# SCH_-_Power_Connector.net
KiCad netlist of a schematic drawn in Altium Designer
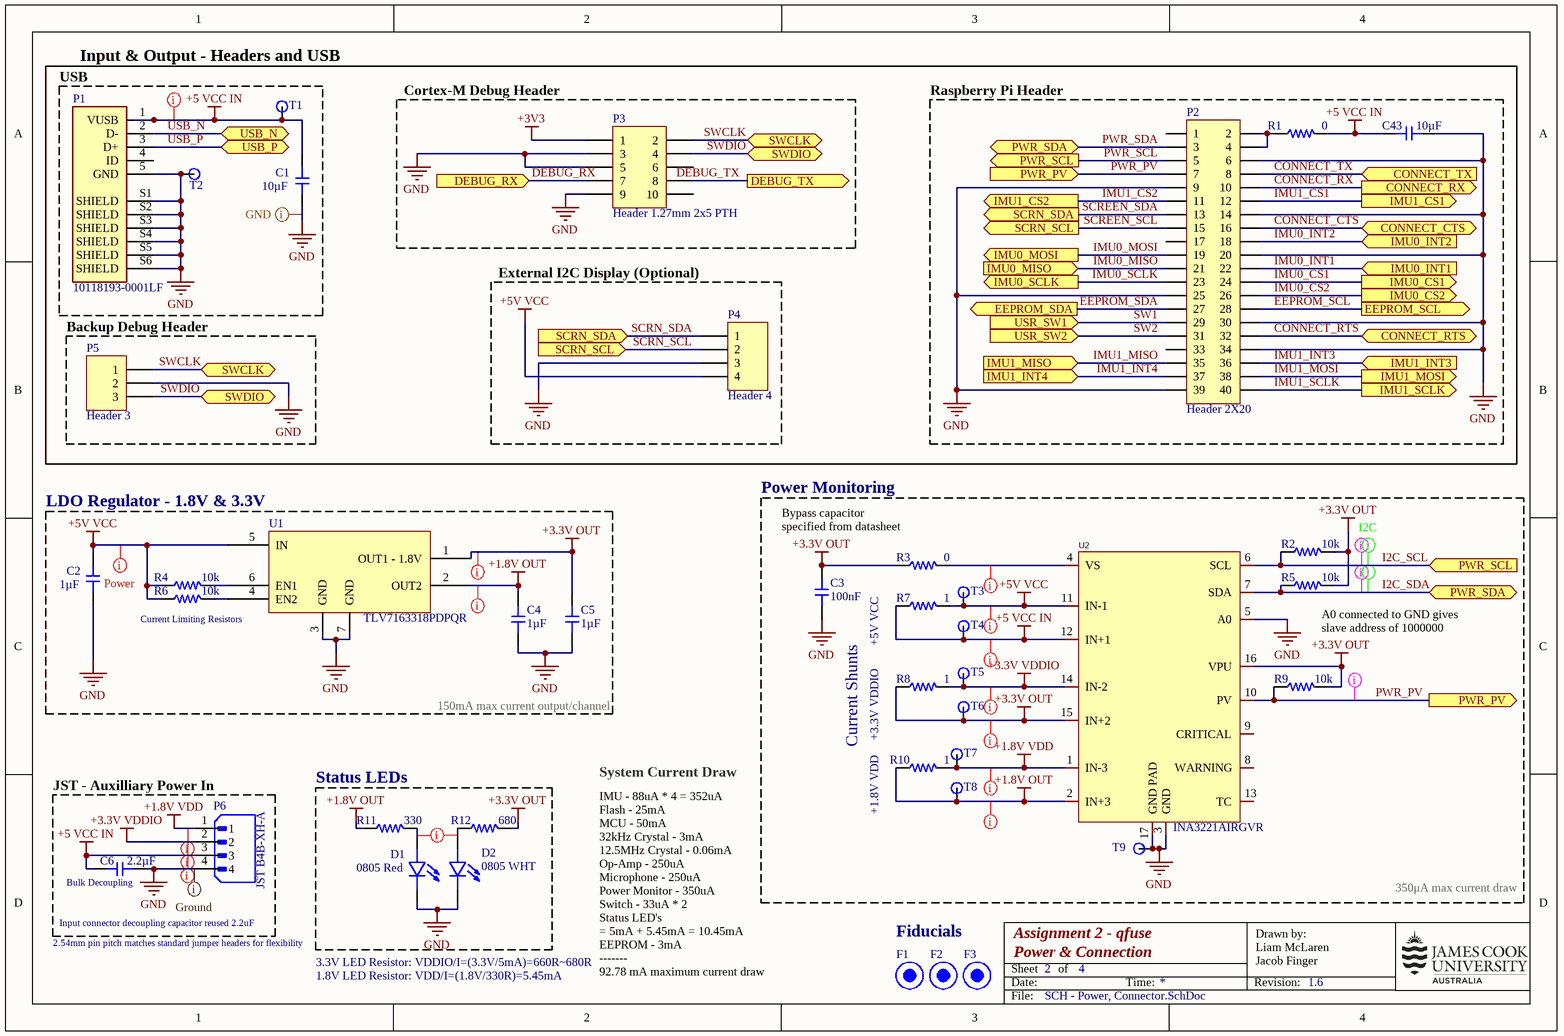
[diagram p0: SCH - Power, Connector.SchDoc]

(export (version "E")
  (design (tool "Eeschema 10.0.6"))
  (components
    (comp (ref "C1")
      (value "10µF")
      (footprint "CAP-0402")
      (description "Capacitor, Ceramic (MLCC), 10uF, ±20%, 6.3V, X5R, ±20%, SMD 0402")
      (fields
        (field (name "MANUFACTURER") "Samsung Electro-Mechanics")
        (field (name "JLCPCB PART NUMBER") "C15525")
      )
      (libsource (lib "Finmac Systems") (part "GRM21BR61H106KE43L"))
    )
    (comp (ref "C2")
      (value "1µF")
      (footprint "CAP-0402")
      (description "Capacitor, Ceramic (MLCC), 1uF, ±10%, 25V, X5R, ±10%, SMD 0402")
      (fields
        (field (name "MANUFACTURER PART NUMBER") "CL05A105KA5NQNC")
        (field (name "MANUFACTURER") "Samsung Electro-Mechanics")
      )
      (libsource (lib "Finmac Systems") (part "GRM21BR61H106KE43L"))
    )
    (comp (ref "C3")
      (value "100nF")
      (footprint "CAP-0402")
      (description "Capacitor, Ceramic (MLCC), 100nF, ±10%, 50V, X7R, ±10%, SMD 0402")
      (fields (field (name "JLCPCB PART NUMBER") "C307331") (field (name "JLCPCB BASIC PART") "Yes"))
      (libsource (lib "Finmac Systems") (part "GRM21BR61H106KE43L"))
    )
    (comp (ref "C4")
      (value "1µF")
      (footprint "CAP-0402")
      (description "Capacitor, Ceramic (MLCC), 1uF, ±10%, 25V, X5R, ±10%, SMD 0402")
      (fields
        (field (name "MANUFACTURER PART NUMBER") "CL05A105KA5NQNC")
        (field (name "MANUFACTURER") "Samsung Electro-Mechanics")
      )
      (libsource (lib "Finmac Systems") (part "GRM21BR61H106KE43L"))
    )
    (comp (ref "C5")
      (value "1µF")
      (footprint "CAP-0402")
      (description "Capacitor, Ceramic (MLCC), 1uF, ±10%, 25V, X5R, ±10%, SMD 0402")
      (fields
        (field (name "MANUFACTURER PART NUMBER") "CL05A105KA5NQNC")
        (field (name "MANUFACTURER") "Samsung Electro-Mechanics")
      )
      (libsource (lib "Finmac Systems") (part "GRM21BR61H106KE43L"))
    )
    (comp (ref "C6")
      (value "2.2µF")
      (footprint "CAP-0402")
      (description "Capacitor, Ceramic (MLCC), 2.2uF, ±20%, 6.3V, X5R, ±20%, SMD 0402")
      (fields (field (name "TOLERANCE") "20%") (field (name "JLCPCB PART NUMBER") "C12530"))
      (libsource (lib "Finmac Systems") (part "GRM21BR61H106KE43L"))
    )
    (comp (ref "C43")
      (value "10µF")
      (footprint "CAP-0402")
      (description "Capacitor, Ceramic (MLCC), 10uF, ±20%, 6.3V, X5R, ±20%, SMD 0402")
      (fields
        (field (name "MANUFACTURER") "Samsung Electro-Mechanics")
        (field (name "JLCPCB PART NUMBER") "C15525")
      )
      (libsource (lib "Finmac Systems") (part "GRM21BR61H106KE43L"))
    )
    (comp (ref "D1")
      (value "0805 Red")
      (footprint "NCD0805R1")
      (fields
        (field (name "MF") "Foshan NationStar Optoelectronics")
        (field (name "MP") "NCD0805R1")
        (field (name "LCSC PART #") "C84256")
      )
      (libsource (lib "qfuse_sch_lib") (part "NCD0805R1"))
    )
    (comp (ref "D2")
      (value "0805 WHT")
      (footprint "LED_KT-0805G")
      (description "0805 WHT LED ¦ 25mA ¦ Vf = 2.6-3.2V - 0805 Light Emitting Diodes (LED) ROHS")
      (fields (field (name "MF") "Hubei KENTO Elec") (field (name "MP") "KT-0805W"))
      (libsource (lib "qfuse_sch_lib") (part "KT-0805W"))
    )
    (comp (ref "F1")
      (value "Fiducial Pad")
      (footprint "Fiducial")
      (description "1x2mm Fiducial Pad")
      (libsource (lib "DatumPenLibrary") (part "Fiducial"))
    )
    (comp (ref "F2")
      (value "Fiducial Pad")
      (footprint "Fiducial")
      (description "1x2mm Fiducial Pad")
      (libsource (lib "DatumPenLibrary") (part "Fiducial"))
    )
    (comp (ref "F3")
      (value "Fiducial Pad")
      (footprint "Fiducial")
      (description "1x2mm Fiducial Pad")
      (libsource (lib "DatumPenLibrary") (part "Fiducial"))
    )
    (comp (ref "P1")
      (value "10118193-0001LF")
      (footprint "FCI_10118193-0001LF")
      (description "USB - micro B USB 2.0 Receptacle Connector 5 Position Surface Mount, Right Angle; Through Hole")
      (fields (field (name "MF") "Amphenol ICC") (field (name "JLCPCB PART NUMBER") "C132562"))
      (libsource (lib "qfuse_sch_lib") (part "CMP-045-000000-8"))
    )
    (comp (ref "P2")
      (value "Header 2X20")
      (footprint "HDR2X20")
      (description "Header, 20-Pin, Dual row, 2.54mm Pin Pitch")
      (fields (field (name "PUBLISHER") "Altium Limited"))
      (libsource (lib "qfuse_sch_lib") (part "HDR2X20"))
    )
    (comp (ref "P3")
      (value "Header 1.27mm 2x5 PTH")
      (footprint "Header 1.27mm 2x5 PTH")
      (description "Header 1.27mm pitch, 2x5, PTH through hole")
      (fields (field (name "SOURCE") "JCULibrary.SchLib"))
      (libsource (lib "qfuse_sch_lib") (part "CMP-005-0002-2"))
    )
    (comp (ref "P4")
      (value "Header 4")
      (footprint "HDR1X4")
      (description "Header, 4-Pin")
      (fields (field (name "PUBLISHER") "Altium Limited"))
      (libsource (lib "qfuse_sch_lib") (part "CMP-002-00124-1"))
    )
    (comp (ref "P5")
      (value "Header 3")
      (footprint "HDR1X3")
      (description "Header, 3-Pin")
      (fields (field (name "PUBLISHER") "Altium Limited"))
      (libsource (lib "James Cook University") (part "Header 3H"))
    )
    (comp (ref "P6")
      (value "JST B4B-XH-A")
      (footprint "JST_B4B-XH-A")
      (fields (field (name "MF") "JST Sales") (field (name "MP") "B4B-XH-A(LF)(SN)"))
      (libsource (lib "DatumPenLibrary") (part "B4B-XH-A"))
    )
    (comp (ref "R1")
      (value "0")
      (footprint "RES-0402")
      (description "Resistor, 0Ω, ±1%, 62.5mW, 50V, ±800ppm/℃, -55℃~+155℃, SMD 0402")
      (fields (field (name "JLCPCB PART NUMBER") "C17168") (field (name "JLCPCB BASIC PART") "Yes"))
      (libsource (lib "Finmac Systems") (part "1206W4F7500T5E"))
    )
    (comp (ref "R2")
      (value "10k")
      (footprint "RES-0402")
      (description "Resistor, 10kΩ, ±1%, 62.5mW, 50V, ±100ppm/℃, -55℃~+155℃, SMD 0402")
      (fields (field (name "JLCPCB PART NUMBER") "C25744") (field (name "TOLERANCE") "1%"))
      (libsource (lib "Finmac Systems") (part "1206W4F7500T5E"))
    )
    (comp (ref "R3")
      (value "0")
      (footprint "RES-0402")
      (description "Resistor, 0Ω, ±1%, 62.5mW, 50V, ±800ppm/℃, -55℃~+155℃, SMD 0402")
      (fields (field (name "JLCPCB PART NUMBER") "C17168") (field (name "JLCPCB BASIC PART") "Yes"))
      (libsource (lib "Finmac Systems") (part "1206W4F7500T5E"))
    )
    (comp (ref "R4")
      (value "10k")
      (footprint "RES-0402")
      (description "Resistor, 10kΩ, ±1%, 62.5mW, 50V, ±100ppm/℃, -55℃~+155℃, SMD 0402")
      (fields (field (name "JLCPCB PART NUMBER") "C25744") (field (name "TOLERANCE") "1%"))
      (libsource (lib "Finmac Systems") (part "1206W4F7500T5E"))
    )
    (comp (ref "R5")
      (value "10k")
      (footprint "RES-0402")
      (description "Resistor, 10kΩ, ±1%, 62.5mW, 50V, ±100ppm/℃, -55℃~+155℃, SMD 0402")
      (fields (field (name "JLCPCB PART NUMBER") "C25744") (field (name "TOLERANCE") "1%"))
      (libsource (lib "Finmac Systems") (part "1206W4F7500T5E"))
    )
    (comp (ref "R6")
      (value "10k")
      (footprint "RES-0402")
      (description "Resistor, 10kΩ, ±1%, 62.5mW, 50V, ±100ppm/℃, -55℃~+155℃, SMD 0402")
      (fields (field (name "JLCPCB PART NUMBER") "C25744") (field (name "TOLERANCE") "1%"))
      (libsource (lib "Finmac Systems") (part "1206W4F7500T5E"))
    )
    (comp (ref "R7")
      (value "1")
      (footprint "RES-0402")
      (description "Resistor, 1Ω, ±1%, 62.5mW, 50V, ±200ppm/℃, -55℃~+155℃, SMD 0402")
      (fields (field (name "MANUFACTURER") "Uniroyal") (field (name "JLCPCB BASIC PART") "Yes"))
      (libsource (lib "Finmac Systems") (part "1206W4F7500T5E"))
    )
    (comp (ref "R8")
      (value "1")
      (footprint "RES-0402")
      (description "Resistor, 1Ω, ±1%, 62.5mW, 50V, ±200ppm/℃, -55℃~+155℃, SMD 0402")
      (fields (field (name "MANUFACTURER") "Uniroyal") (field (name "JLCPCB BASIC PART") "Yes"))
      (libsource (lib "Finmac Systems") (part "1206W4F7500T5E"))
    )
    (comp (ref "R9")
      (value "10k")
      (footprint "RES-0402")
      (description "Resistor, 10kΩ, ±1%, 62.5mW, 50V, ±100ppm/℃, -55℃~+155℃, SMD 0402")
      (fields (field (name "JLCPCB PART NUMBER") "C25744") (field (name "TOLERANCE") "1%"))
      (libsource (lib "Finmac Systems") (part "1206W4F7500T5E"))
    )
    (comp (ref "R10")
      (value "1")
      (footprint "RES-0402")
      (description "Resistor, 1Ω, ±1%, 62.5mW, 50V, ±200ppm/℃, -55℃~+155℃, SMD 0402")
      (fields (field (name "MANUFACTURER") "Uniroyal") (field (name "JLCPCB BASIC PART") "Yes"))
      (libsource (lib "Finmac Systems") (part "1206W4F7500T5E"))
    )
    (comp (ref "R11")
      (value "330")
      (footprint "RES-0402")
      (description "Resistor, 330Ω, ±1%, 62.5mW, 50V, ±100ppm/℃, -55℃~+155℃, SMD 0402")
      (fields (field (name "MANUFACTURER") "Uniroyal") (field (name "TOLERANCE") "1%"))
      (libsource (lib "Finmac Systems") (part "1206W4F7500T5E"))
    )
    (comp (ref "R12")
      (value "680")
      (footprint "RES-0402")
      (description "Resistor, 680Ω, ±1%, 62.5mW, 50V, ±100ppm/℃, -55℃~+155℃, SMD 0402")
      (fields
        (field (name "MANUFACTURER") "Uniroyal")
        (field (name "MANUFACTURER PART NUMBER") "0402WGF6800TCE")
      )
      (libsource (lib "Finmac Systems") (part "1206W4F7500T5E"))
    )
    (comp (ref "T1")
      (value "TP")
      (footprint "TestPoint")
      (libsource (lib "DatumPenLibrary") (part "TestPoint"))
    )
    (comp (ref "T2")
      (value "TP")
      (footprint "TestPoint")
      (libsource (lib "DatumPenLibrary") (part "TestPoint"))
    )
    (comp (ref "T3")
      (value "TP")
      (footprint "TestPoint")
      (libsource (lib "DatumPenLibrary") (part "TestPoint"))
    )
    (comp (ref "T4")
      (value "TP")
      (footprint "TestPoint")
      (libsource (lib "DatumPenLibrary") (part "TestPoint"))
    )
    (comp (ref "T5")
      (value "TP")
      (footprint "TestPoint")
      (libsource (lib "DatumPenLibrary") (part "TestPoint"))
    )
    (comp (ref "T6")
      (value "TP")
      (footprint "TestPoint")
      (libsource (lib "DatumPenLibrary") (part "TestPoint"))
    )
    (comp (ref "T7")
      (value "TP")
      (footprint "TestPoint")
      (libsource (lib "DatumPenLibrary") (part "TestPoint"))
    )
    (comp (ref "T8")
      (value "TP")
      (footprint "TestPoint")
      (libsource (lib "DatumPenLibrary") (part "TestPoint"))
    )
    (comp (ref "T9")
      (value "TP")
      (footprint "TestPoint")
      (libsource (lib "DatumPenLibrary") (part "TestPoint"))
    )
    (comp (ref "U1")
      (value "TLV7163318PDPQR")
      (footprint "XDFN-6_L1.2-W1.2-P0.40-BL-EP")
      (fields (field (name "JLCPCB PART NUMBER") "C2859836"))
      (libsource (lib "qfuse_sch_lib") (part "TLV7163318PDPQR"))
    )
    (comp (ref "U2")
      (value "INA3221AIRGVR")
      (footprint "QFN-16_L4.0-W4.0-P0.65-TL-EP2.2")
      (description "Texas Instruments INA3221AIRGVR - QFN-16-EP(4x4) Current Sense Amplifiers ROHS")
      (fields (field (name "MANUFACTURER") "TI(德州仪器)") (field (name "JLCPCB PART NUMBER") "C181255"))
      (libsource (lib "qfuse_sch_lib") (part "INA3221AIRGVR"))
    )
  )
  (nets
    (net (code "1") (name "+1.8V OUT") (class "Default")
      (node (ref "C4") (pin "2") (pinfunction "2_2") (pintype "passive"))
      (node (ref "R10") (pin "1") (pinfunction "1_1") (pintype "passive"))
      (node (ref "R11") (pin "1") (pinfunction "1_1") (pintype "passive"))
      (node (ref "T8") (pin "1") (pinfunction "TP_1") (pintype "passive"))
      (node (ref "U1") (pin "2") (pinfunction "OUT2_2") (pintype "passive"))
      (node (ref "U2") (pin "2") (pinfunction "IN+3_2") (pintype "passive"))
    )
    (net (code "2") (name "+1.8V VDD") (class "Default")
      (node (ref "P6") (pin "1") (pinfunction "1_1") (pintype "passive"))
      (node (ref "R10") (pin "2") (pinfunction "2_2") (pintype "passive"))
      (node (ref "T7") (pin "1") (pinfunction "TP_1") (pintype "passive"))
      (node (ref "U2") (pin "1") (pinfunction "IN-3_1") (pintype "passive"))
    )
    (net (code "3") (name "+3.3V OUT") (class "Default")
      (node (ref "C3") (pin "2") (pinfunction "2_2") (pintype "passive"))
      (node (ref "C5") (pin "2") (pinfunction "2_2") (pintype "passive"))
      (node (ref "R12") (pin "2") (pinfunction "2_2") (pintype "passive"))
      (node (ref "R2") (pin "2") (pinfunction "2_2") (pintype "passive"))
      (node (ref "R3") (pin "1") (pinfunction "1_1") (pintype "passive"))
      (node (ref "R5") (pin "2") (pinfunction "2_2") (pintype "passive"))
      (node (ref "R8") (pin "1") (pinfunction "1_1") (pintype "passive"))
      (node (ref "R9") (pin "2") (pinfunction "2_2") (pintype "passive"))
      (node (ref "T6") (pin "1") (pinfunction "TP_1") (pintype "passive"))
      (node (ref "U1") (pin "1") (pinfunction "OUT1_-_1.8V_1") (pintype "passive"))
      (node (ref "U2") (pin "15") (pinfunction "IN+2_15") (pintype "passive"))
      (node (ref "U2") (pin "16") (pinfunction "VPU_16") (pintype "passive"))
    )
    (net (code "4") (name "+3.3V VDDIO") (class "Default")
      (node (ref "P6") (pin "2") (pinfunction "2_2") (pintype "passive"))
      (node (ref "R8") (pin "2") (pinfunction "2_2") (pintype "passive"))
      (node (ref "T5") (pin "1") (pinfunction "TP_1") (pintype "passive"))
      (node (ref "U2") (pin "14") (pinfunction "IN-2_14") (pintype "passive"))
    )
    (net (code "5") (name "+3V3") (class "Default")
      (node (ref "P3") (pin "1") (pinfunction "1_1") (pintype "passive"))
    )
    (net (code "6") (name "+5 VCC IN") (class "Default")
      (node (ref "C1") (pin "2") (pinfunction "2_2") (pintype "passive"))
      (node (ref "C43") (pin "2") (pinfunction "2_2") (pintype "passive"))
      (node (ref "C6") (pin "2") (pinfunction "2_2") (pintype "passive"))
      (node (ref "P1") (pin "1") (pinfunction "VUSB_1") (pintype "passive"))
      (node (ref "P6") (pin "3") (pinfunction "3_3") (pintype "passive"))
      (node (ref "R1") (pin "2") (pinfunction "2_2") (pintype "passive"))
      (node (ref "R7") (pin "1") (pinfunction "1_1") (pintype "passive"))
      (node (ref "T1") (pin "1") (pinfunction "TP_1") (pintype "passive"))
      (node (ref "T4") (pin "1") (pinfunction "TP_1") (pintype "passive"))
      (node (ref "U2") (pin "12") (pinfunction "IN+1_12") (pintype "passive"))
    )
    (net (code "7") (name "+5V VCC") (class "Default")
      (node (ref "C2") (pin "2") (pinfunction "2_2") (pintype "passive"))
      (node (ref "P4") (pin "4") (pinfunction "4_4") (pintype "passive"))
      (node (ref "R4") (pin "1") (pinfunction "1_1") (pintype "passive"))
      (node (ref "R6") (pin "1") (pinfunction "1_1") (pintype "passive"))
      (node (ref "R7") (pin "2") (pinfunction "2_2") (pintype "passive"))
      (node (ref "T3") (pin "1") (pinfunction "TP_1") (pintype "passive"))
      (node (ref "U1") (pin "5") (pinfunction "IN_5") (pintype "passive"))
      (node (ref "U2") (pin "11") (pinfunction "IN-1_11") (pintype "passive"))
    )
    (net (code "8") (name "/CONNECT_CTS") (class "Default")
      (node (ref "P2") (pin "16") (pinfunction "16_16") (pintype "passive"))
    )
    (net (code "9") (name "/CONNECT_RTS") (class "Default")
      (node (ref "P2") (pin "32") (pinfunction "32_32") (pintype "passive"))
    )
    (net (code "10") (name "/CONNECT_RX") (class "Default")
      (node (ref "P2") (pin "10") (pinfunction "10_10") (pintype "passive"))
    )
    (net (code "11") (name "/CONNECT_TX") (class "Default")
      (node (ref "P2") (pin "8") (pinfunction "8_8") (pintype "passive"))
    )
    (net (code "12") (name "/DEBUG_RX") (class "Default")
      (node (ref "P3") (pin "7") (pinfunction "7_7") (pintype "passive"))
    )
    (net (code "13") (name "/DEBUG_TX") (class "Default")
      (node (ref "P3") (pin "8") (pinfunction "8_8") (pintype "passive"))
    )
    (net (code "14") (name "/EEPROM_SCL") (class "Default")
      (node (ref "P2") (pin "28") (pinfunction "28_28") (pintype "passive"))
    )
    (net (code "15") (name "/EEPROM_SDA") (class "Default")
      (node (ref "P2") (pin "27") (pinfunction "27_27") (pintype "passive"))
    )
    (net (code "16") (name "/I2C_SCL") (class "Default")
      (node (ref "P2") (pin "5") (pinfunction "5_5") (pintype "passive"))
      (node (ref "R2") (pin "1") (pinfunction "1_1") (pintype "passive"))
      (node (ref "U2") (pin "6") (pinfunction "SCL_6") (pintype "passive"))
    )
    (net (code "17") (name "/I2C_SDA") (class "Default")
      (node (ref "P2") (pin "3") (pinfunction "3_3") (pintype "passive"))
      (node (ref "R5") (pin "1") (pinfunction "1_1") (pintype "passive"))
      (node (ref "U2") (pin "7") (pinfunction "SDA_7") (pintype "passive"))
    )
    (net (code "18") (name "/IMU0_CS1") (class "Default")
      (node (ref "P2") (pin "24") (pinfunction "24_24") (pintype "passive"))
    )
    (net (code "19") (name "/IMU0_CS2") (class "Default")
      (node (ref "P2") (pin "26") (pinfunction "26_26") (pintype "passive"))
    )
    (net (code "20") (name "/IMU0_INT1") (class "Default")
      (node (ref "P2") (pin "22") (pinfunction "22_22") (pintype "passive"))
    )
    (net (code "21") (name "/IMU0_INT2") (class "Default")
      (node (ref "P2") (pin "18") (pinfunction "18_18") (pintype "passive"))
    )
    (net (code "22") (name "/IMU0_MISO") (class "Default")
      (node (ref "P2") (pin "21") (pinfunction "21_21") (pintype "passive"))
    )
    (net (code "23") (name "/IMU0_MOSI") (class "Default")
      (node (ref "P2") (pin "19") (pinfunction "19_19") (pintype "passive"))
    )
    (net (code "24") (name "/IMU0_SCLK") (class "Default")
      (node (ref "P2") (pin "23") (pinfunction "23_23") (pintype "passive"))
    )
    (net (code "25") (name "/IMU1_CS1") (class "Default")
      (node (ref "P2") (pin "12") (pinfunction "12_12") (pintype "passive"))
    )
    (net (code "26") (name "/IMU1_CS2") (class "Default")
      (node (ref "P2") (pin "11") (pinfunction "11_11") (pintype "passive"))
    )
    (net (code "27") (name "/IMU1_INT3") (class "Default")
      (node (ref "P2") (pin "36") (pinfunction "36_36") (pintype "passive"))
    )
    (net (code "28") (name "/IMU1_INT4") (class "Default")
      (node (ref "P2") (pin "37") (pinfunction "37_37") (pintype "passive"))
    )
    (net (code "29") (name "/IMU1_MISO") (class "Default")
      (node (ref "P2") (pin "35") (pinfunction "35_35") (pintype "passive"))
    )
    (net (code "30") (name "/IMU1_MOSI") (class "Default")
      (node (ref "P2") (pin "38") (pinfunction "38_38") (pintype "passive"))
    )
    (net (code "31") (name "/IMU1_SCLK") (class "Default")
      (node (ref "P2") (pin "40") (pinfunction "40_40") (pintype "passive"))
    )
    (net (code "32") (name "/PWR_PV") (class "Default")
      (node (ref "P2") (pin "7") (pinfunction "7_7") (pintype "passive"))
      (node (ref "R9") (pin "1") (pinfunction "1_1") (pintype "passive"))
      (node (ref "U2") (pin "10") (pinfunction "PV_10") (pintype "passive"))
    )
    (net (code "33") (name "/SCREEN_SCL") (class "Default")
      (node (ref "P2") (pin "15") (pinfunction "15_15") (pintype "passive"))
      (node (ref "P4") (pin "2") (pinfunction "2_2") (pintype "passive"))
    )
    (net (code "34") (name "/SCREEN_SDA") (class "Default")
      (node (ref "P2") (pin "13") (pinfunction "13_13") (pintype "passive"))
      (node (ref "P4") (pin "1") (pinfunction "1_1") (pintype "passive"))
    )
    (net (code "35") (name "/SW1") (class "Default")
      (node (ref "P2") (pin "29") (pinfunction "29_29") (pintype "passive"))
    )
    (net (code "36") (name "/SW2") (class "Default")
      (node (ref "P2") (pin "31") (pinfunction "31_31") (pintype "passive"))
    )
    (net (code "37") (name "/SWCLK") (class "Default")
      (node (ref "P3") (pin "2") (pinfunction "2_2") (pintype "passive"))
      (node (ref "P5") (pin "1") (pinfunction "1_1") (pintype "passive"))
    )
    (net (code "38") (name "/SWDIO") (class "Default")
      (node (ref "P3") (pin "4") (pinfunction "4_4") (pintype "passive"))
      (node (ref "P5") (pin "3") (pinfunction "3_3") (pintype "passive"))
    )
    (net (code "39") (name "/USB_N") (class "Default")
      (node (ref "P1") (pin "2") (pinfunction "D-_2") (pintype "passive"))
    )
    (net (code "40") (name "/USB_P") (class "Default")
      (node (ref "P1") (pin "3") (pinfunction "D+_3") (pintype "passive"))
    )
    (net (code "41") (name "GND") (class "Default")
      (node (ref "C1") (pin "1") (pinfunction "1_1") (pintype "passive"))
      (node (ref "C2") (pin "1") (pinfunction "1_1") (pintype "passive"))
      (node (ref "C3") (pin "1") (pinfunction "1_1") (pintype "passive"))
      (node (ref "C4") (pin "1") (pinfunction "1_1") (pintype "passive"))
      (node (ref "C43") (pin "1") (pinfunction "1_1") (pintype "passive"))
      (node (ref "C5") (pin "1") (pinfunction "1_1") (pintype "passive"))
      (node (ref "C6") (pin "1") (pinfunction "1_1") (pintype "passive"))
      (node (ref "D1") (pin "C") (pinfunction "C_C") (pintype "passive"))
      (node (ref "D2") (pin "C") (pinfunction "C_C") (pintype "passive"))
      (node (ref "P1") (pin "5") (pinfunction "GND_5") (pintype "passive"))
      (node (ref "P1") (pin "S1") (pinfunction "SHIELD_S1") (pintype "passive"))
      (node (ref "P1") (pin "S2") (pinfunction "SHIELD_S2") (pintype "passive"))
      (node (ref "P1") (pin "S3") (pinfunction "SHIELD_S3") (pintype "passive"))
      (node (ref "P1") (pin "S4") (pinfunction "SHIELD_S4") (pintype "passive"))
      (node (ref "P1") (pin "S5") (pinfunction "SHIELD_S5") (pintype "passive"))
      (node (ref "P1") (pin "S6") (pinfunction "SHIELD_S6") (pintype "passive"))
      (node (ref "P2") (pin "14") (pinfunction "14_14") (pintype "passive"))
      (node (ref "P2") (pin "20") (pinfunction "20_20") (pintype "passive"))
      (node (ref "P2") (pin "25") (pinfunction "25_25") (pintype "passive"))
      (node (ref "P2") (pin "30") (pinfunction "30_30") (pintype "passive"))
      (node (ref "P2") (pin "34") (pinfunction "34_34") (pintype "passive"))
      (node (ref "P2") (pin "39") (pinfunction "39_39") (pintype "passive"))
      (node (ref "P2") (pin "6") (pinfunction "6_6") (pintype "passive"))
      (node (ref "P2") (pin "9") (pinfunction "9_9") (pintype "passive"))
      (node (ref "P3") (pin "3") (pinfunction "3_3") (pintype "passive"))
      (node (ref "P3") (pin "5") (pinfunction "5_5") (pintype "passive"))
      (node (ref "P3") (pin "9") (pinfunction "9_9") (pintype "passive"))
      (node (ref "P4") (pin "3") (pinfunction "3_3") (pintype "passive"))
      (node (ref "P5") (pin "2") (pinfunction "2_2") (pintype "passive"))
      (node (ref "P6") (pin "4") (pinfunction "4_4") (pintype "passive"))
      (node (ref "T2") (pin "1") (pinfunction "TP_1") (pintype "passive"))
      (node (ref "T9") (pin "1") (pinfunction "TP_1") (pintype "passive"))
      (node (ref "U1") (pin "3") (pinfunction "GND_3") (pintype "passive"))
      (node (ref "U1") (pin "7") (pinfunction "GND_7") (pintype "passive"))
      (node (ref "U2") (pin "17") (pinfunction "GND_PAD_17") (pintype "passive"))
      (node (ref "U2") (pin "3") (pinfunction "GND_3") (pintype "passive"))
      (node (ref "U2") (pin "5") (pinfunction "A0_5") (pintype "passive"))
    )
    (net (code "42") (name "Net-(D1-PadA)") (class "Default")
      (node (ref "D1") (pin "A") (pinfunction "A_A") (pintype "passive"))
      (node (ref "R11") (pin "2") (pinfunction "2_2") (pintype "passive"))
    )
    (net (code "43") (name "Net-(D2-PadA)") (class "Default")
      (node (ref "D2") (pin "A") (pinfunction "A_A") (pintype "passive"))
      (node (ref "R12") (pin "1") (pinfunction "1_1") (pintype "passive"))
    )
    (net (code "44") (name "Net-(P2-Pad2)") (class "Default")
      (node (ref "P2") (pin "2") (pinfunction "2_2") (pintype "passive"))
      (node (ref "P2") (pin "4") (pinfunction "4_4") (pintype "passive"))
      (node (ref "R1") (pin "1") (pinfunction "1_1") (pintype "passive"))
    )
    (net (code "45") (name "Net-(U1-EN1)") (class "Default")
      (node (ref "R4") (pin "2") (pinfunction "2_2") (pintype "passive"))
      (node (ref "U1") (pin "6") (pinfunction "EN1_6") (pintype "passive"))
    )
    (net (code "46") (name "Net-(U1-EN2)") (class "Default")
      (node (ref "R6") (pin "2") (pinfunction "2_2") (pintype "passive"))
      (node (ref "U1") (pin "4") (pinfunction "EN2_4") (pintype "passive"))
    )
    (net (code "47") (name "Net-(U2-VS)") (class "Default")
      (node (ref "R3") (pin "2") (pinfunction "2_2") (pintype "passive"))
      (node (ref "U2") (pin "4") (pinfunction "VS_4") (pintype "passive"))
    )
    (net (code "48") (name "unconnected-(P1-ID-Pad4)") (class "Default")
      (node (ref "P1") (pin "4") (pinfunction "ID_4") (pintype "passive"))
    )
    (net (code "49") (name "unconnected-(P2-Pad1)") (class "Default")
      (node (ref "P2") (pin "1") (pinfunction "1_1") (pintype "passive"))
    )
    (net (code "50") (name "unconnected-(P2-Pad17)") (class "Default")
      (node (ref "P2") (pin "17") (pinfunction "17_17") (pintype "passive"))
    )
    (net (code "51") (name "unconnected-(P2-Pad33)") (class "Default")
      (node (ref "P2") (pin "33") (pinfunction "33_33") (pintype "passive"))
    )
    (net (code "52") (name "unconnected-(P3-Pad6)") (class "Default")
      (node (ref "P3") (pin "6") (pinfunction "6_6") (pintype "passive"))
    )
    (net (code "53") (name "unconnected-(P3-Pad10)") (class "Default")
      (node (ref "P3") (pin "10") (pinfunction "10_10") (pintype "passive"))
    )
    (net (code "54") (name "unconnected-(U2-CRITICAL-Pad9)") (class "Default")
      (node (ref "U2") (pin "9") (pinfunction "CRITICAL_9") (pintype "passive"))
    )
    (net (code "55") (name "unconnected-(U2-TC-Pad13)") (class "Default")
      (node (ref "U2") (pin "13") (pinfunction "TC_13") (pintype "passive"))
    )
    (net (code "56") (name "unconnected-(U2-WARNING-Pad8)") (class "Default")
      (node (ref "U2") (pin "8") (pinfunction "WARNING_8") (pintype "passive"))
    )
  )
)
